# Voltage_supply_reference.net
KiCad netlist of a schematic drawn in Altium Designer
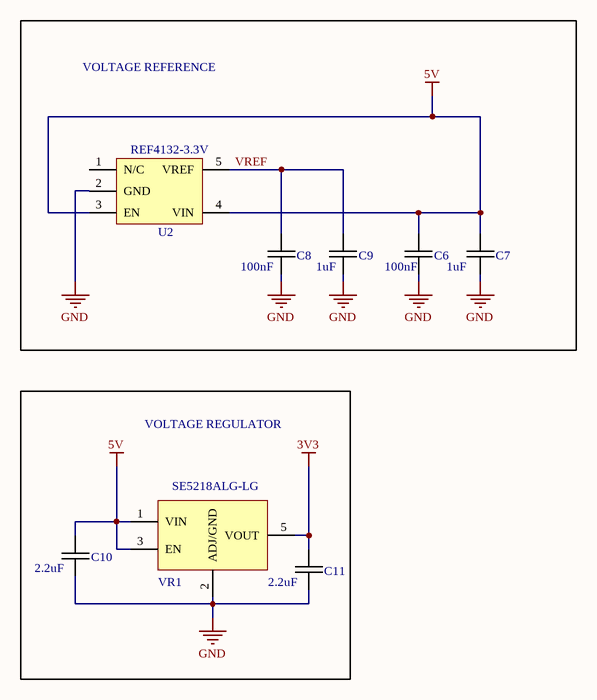
[diagram p0: Voltage supply & reference.SchDoc]

(export (version "E")
  (design (tool "Eeschema 10.0.6"))
  (components
    (comp (ref "C6")
      (value "100nF")
      (footprint "0603C")
      (libsource (lib "TAVU Altium library") (part "0603C"))
    )
    (comp (ref "C7") (value "1uF") (footprint "0603C") (libsource (lib "TAVU Altium library") (part "0603C")))
    (comp (ref "C8")
      (value "100nF")
      (footprint "0603C")
      (libsource (lib "TAVU Altium library") (part "0603C"))
    )
    (comp (ref "C9") (value "1uF") (footprint "0603C") (libsource (lib "TAVU Altium library") (part "0603C")))
    (comp (ref "C10")
      (value "2.2uF")
      (footprint "0603C")
      (libsource (lib "TAVU Altium library") (part "0603C"))
    )
    (comp (ref "C11")
      (value "2.2uF")
      (footprint "0603C")
      (libsource (lib "TAVU Altium library") (part "0603C"))
    )
    (comp (ref "U2")
      (value "REF4132-3.3V")
      (footprint "SOT-23-5")
      (libsource (lib "TAVU Altium library") (part "REF4132-3.3V"))
    )
    (comp (ref "VR1")
      (value "SE5218ALG-LG")
      (footprint "SOT-23-5")
      (libsource (lib "TAVU Altium library") (part "VREG 3V3"))
    )
  )
  (nets
    (net (code "1") (name "/VREF") (class "Default")
      (node (ref "C8") (pin "2") (pinfunction "2_2") (pintype "passive"))
      (node (ref "C9") (pin "2") (pinfunction "2_2") (pintype "passive"))
      (node (ref "U2") (pin "5") (pinfunction "VREF_5") (pintype "passive"))
    )
    (net (code "2") (name "3V3") (class "Default")
      (node (ref "C11") (pin "2") (pinfunction "2_2") (pintype "passive"))
      (node (ref "VR1") (pin "5") (pinfunction "VOUT_5") (pintype "passive"))
    )
    (net (code "3") (name "5V") (class "Default")
      (node (ref "C10") (pin "2") (pinfunction "2_2") (pintype "passive"))
      (node (ref "C6") (pin "2") (pinfunction "2_2") (pintype "passive"))
      (node (ref "C7") (pin "2") (pinfunction "2_2") (pintype "passive"))
      (node (ref "U2") (pin "3") (pinfunction "EN_3") (pintype "passive"))
      (node (ref "U2") (pin "4") (pinfunction "VIN_4") (pintype "passive"))
      (node (ref "VR1") (pin "1") (pinfunction "VIN_1") (pintype "passive"))
      (node (ref "VR1") (pin "3") (pinfunction "EN_3") (pintype "passive"))
    )
    (net (code "4") (name "GND") (class "Default")
      (node (ref "C10") (pin "1") (pinfunction "1_1") (pintype "passive"))
      (node (ref "C11") (pin "1") (pinfunction "1_1") (pintype "passive"))
      (node (ref "C6") (pin "1") (pinfunction "1_1") (pintype "passive"))
      (node (ref "C7") (pin "1") (pinfunction "1_1") (pintype "passive"))
      (node (ref "C8") (pin "1") (pinfunction "1_1") (pintype "passive"))
      (node (ref "C9") (pin "1") (pinfunction "1_1") (pintype "passive"))
      (node (ref "U2") (pin "2") (pinfunction "GND_2") (pintype "passive"))
      (node (ref "VR1") (pin "2") (pinfunction "ADJ/GND_2") (pintype "passive"))
    )
    (net (code "5") (name "unconnected-(U2-N{slash}C-Pad1)") (class "Default")
      (node (ref "U2") (pin "1") (pinfunction "N/C_1") (pintype "passive"))
    )
  )
)
